# wssf_arduino_nano_client.net
KiCad netlist of a schematic drawn in EAGLE
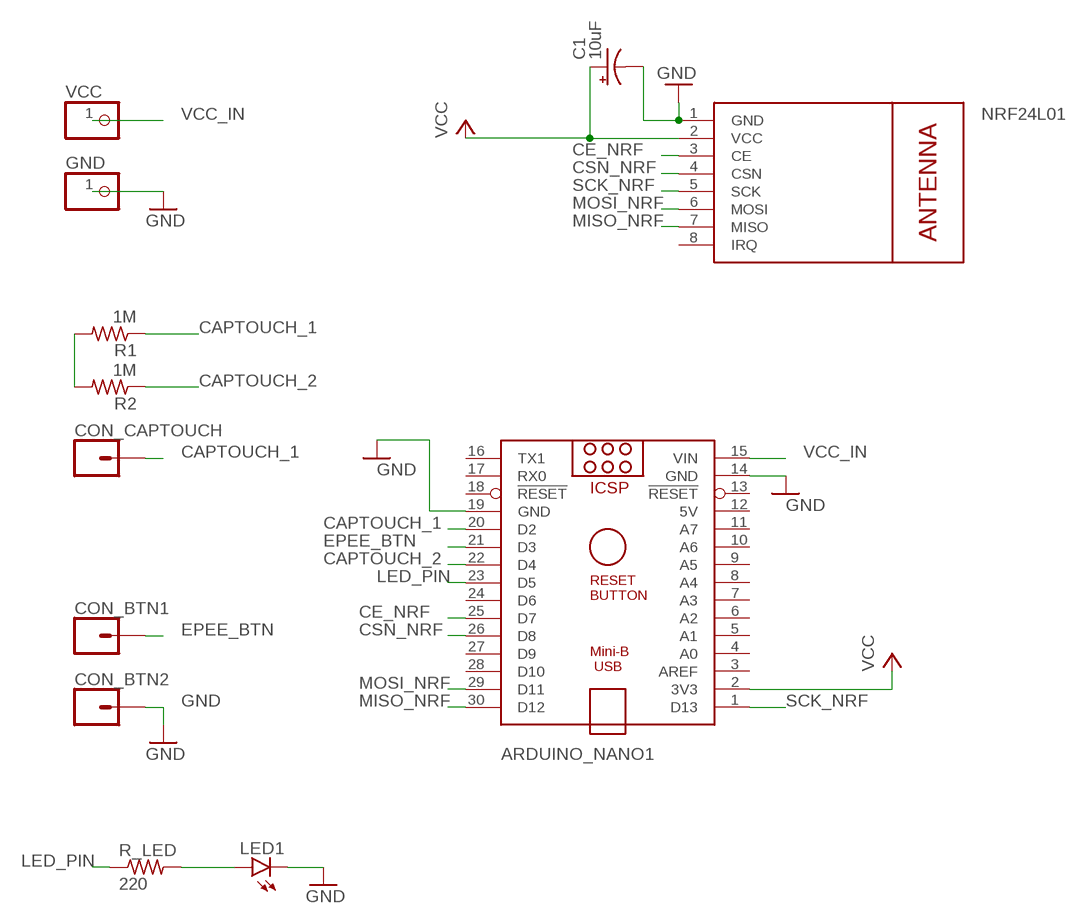
[diagram p0: schematic, sheet 1]

(export (version "E")
  (design (tool "Eeschema 10.0.6"))
  (components
    (comp (ref "ARDUINO_NANO1")
      (value "ARDUINO_NANO")
      (footprint "eagle-import:ARDUINO_NANO")
      (libsource (lib "eagle-import") (part "ARDUINO_NANO"))
    )
    (comp (ref "C1")
      (value "10uF")
      (footprint "eagle-import:E2-5")
      (libsource (lib "eagle-import") (part "CPOL-USE2-5"))
    )
    (comp (ref "CON_BTN1")
      (value "CONN_01")
      (footprint "eagle-import:1X01")
      (libsource (lib "eagle-import") (part "CONN_01"))
    )
    (comp (ref "CON_BTN2")
      (value "CONN_01")
      (footprint "eagle-import:1X01")
      (libsource (lib "eagle-import") (part "CONN_01"))
    )
    (comp (ref "CON_CAPTOUCH")
      (value "CONN_01")
      (footprint "eagle-import:1X01")
      (libsource (lib "eagle-import") (part "CONN_01"))
    )
    (comp (ref "GND")
      (value "PINHD-1X1")
      (footprint "eagle-import:1X01")
      (libsource (lib "eagle-import") (part "PINHD-1X1"))
    )
    (comp (ref "LED1")
      (value "LED5MM")
      (footprint "eagle-import:LED5MM")
      (libsource (lib "eagle-import") (part "LED5MM"))
    )
    (comp (ref "NRF24L01")
      (value "WIRELESS-NRF24L01")
      (footprint "eagle-import:WIRELESS-NRF24L01")
      (libsource (lib "eagle-import") (part "WIRELESS-NRF24L01"))
    )
    (comp (ref "R1")
      (value "1M")
      (footprint "eagle-import:0204_7")
      (libsource (lib "eagle-import") (part "R-US_0204/7"))
    )
    (comp (ref "R2")
      (value "1M")
      (footprint "eagle-import:0204_7")
      (libsource (lib "eagle-import") (part "R-US_0204/7"))
    )
    (comp (ref "R_LED")
      (value "220")
      (footprint "eagle-import:0204_7")
      (libsource (lib "eagle-import") (part "R-US_0204/7"))
    )
    (comp (ref "VCC")
      (value "PINHD-1X1")
      (footprint "eagle-import:1X01")
      (libsource (lib "eagle-import") (part "PINHD-1X1"))
    )
  )
  (nets
    (net (code "1") (name "/5V") (class "Default")
      (node (ref "ARDUINO_NANO1") (pin "12") (pinfunction "5V_12") (pintype "power_in"))
    )
    (net (code "2") (name "/CAPTOUCH_1") (class "Default")
      (node (ref "ARDUINO_NANO1") (pin "20") (pinfunction "D2_20") (pintype "bidirectional"))
      (node (ref "CON_CAPTOUCH") (pin "1") (pinfunction "1_1") (pintype "passive"))
      (node (ref "R1") (pin "1") (pinfunction "1_1") (pintype "passive"))
    )
    (net (code "3") (name "/CAPTOUCH_2") (class "Default")
      (node (ref "ARDUINO_NANO1") (pin "22") (pinfunction "D4_22") (pintype "bidirectional"))
      (node (ref "R2") (pin "1") (pinfunction "1_1") (pintype "passive"))
    )
    (net (code "4") (name "/CE_NRF") (class "Default")
      (node (ref "ARDUINO_NANO1") (pin "25") (pinfunction "D7_25") (pintype "bidirectional"))
      (node (ref "NRF24L01") (pin "3") (pinfunction "CE_3") (pintype "bidirectional"))
    )
    (net (code "5") (name "/CSN_NRF") (class "Default")
      (node (ref "ARDUINO_NANO1") (pin "26") (pinfunction "D8_26") (pintype "bidirectional"))
      (node (ref "NRF24L01") (pin "4") (pinfunction "CSN_4") (pintype "bidirectional"))
    )
    (net (code "6") (name "/EPEE_BTN") (class "Default")
      (node (ref "ARDUINO_NANO1") (pin "21") (pinfunction "D3_21") (pintype "bidirectional"))
      (node (ref "CON_BTN1") (pin "1") (pinfunction "1_1") (pintype "passive"))
    )
    (net (code "7") (name "/LED_PIN") (class "Default")
      (node (ref "ARDUINO_NANO1") (pin "23") (pinfunction "D5_23") (pintype "bidirectional"))
      (node (ref "R_LED") (pin "1") (pinfunction "1_1") (pintype "passive"))
    )
    (net (code "8") (name "/MISO_NRF") (class "Default")
      (node (ref "ARDUINO_NANO1") (pin "30") (pinfunction "D12_30") (pintype "bidirectional"))
      (node (ref "NRF24L01") (pin "7") (pinfunction "MISO_7") (pintype "bidirectional"))
    )
    (net (code "9") (name "/MOSI_NRF") (class "Default")
      (node (ref "ARDUINO_NANO1") (pin "29") (pinfunction "D11_29") (pintype "bidirectional"))
      (node (ref "NRF24L01") (pin "6") (pinfunction "MOSI_6") (pintype "bidirectional"))
    )
    (net (code "10") (name "/SCK_NRF") (class "Default")
      (node (ref "ARDUINO_NANO1") (pin "1") (pinfunction "D13_1") (pintype "bidirectional"))
      (node (ref "NRF24L01") (pin "5") (pinfunction "SCK_5") (pintype "bidirectional"))
    )
    (net (code "11") (name "/VCC_IN") (class "Default")
      (node (ref "ARDUINO_NANO1") (pin "15") (pinfunction "VIN_15") (pintype "power_in"))
      (node (ref "VCC") (pin "1") (pinfunction "1_1") (pintype "passive"))
    )
    (net (code "12") (name "GND") (class "Default")
      (node (ref "ARDUINO_NANO1") (pin "14") (pinfunction "GND_14") (pintype "power_in"))
      (node (ref "ARDUINO_NANO1") (pin "19") (pinfunction "GND_19") (pintype "power_in"))
      (node (ref "C1") (pin "-") (pinfunction "-_-") (pintype "passive"))
      (node (ref "CON_BTN2") (pin "1") (pinfunction "1_1") (pintype "passive"))
      (node (ref "GND") (pin "1") (pinfunction "1_1") (pintype "passive"))
      (node (ref "LED1") (pin "K") (pinfunction "C_K") (pintype "passive"))
      (node (ref "NRF24L01") (pin "1") (pinfunction "GND_1") (pintype "power_in"))
    )
    (net (code "13") (name "Net-(LED1-PadA)") (class "Default")
      (node (ref "LED1") (pin "A") (pinfunction "A_A") (pintype "passive"))
      (node (ref "R_LED") (pin "2") (pinfunction "2_2") (pintype "passive"))
    )
    (net (code "14") (name "Net-(R1-Pad2)") (class "Default")
      (node (ref "R1") (pin "2") (pinfunction "2_2") (pintype "passive"))
      (node (ref "R2") (pin "2") (pinfunction "2_2") (pintype "passive"))
    )
    (net (code "15") (name "VCC") (class "Default")
      (node (ref "ARDUINO_NANO1") (pin "2") (pinfunction "3V3_2") (pintype "output"))
      (node (ref "C1") (pin "+") (pinfunction "+_+") (pintype "passive"))
      (node (ref "NRF24L01") (pin "2") (pinfunction "VCC_2") (pintype "power_in"))
    )
    (net (code "16") (name "unconnected-(ARDUINO_NANO1-A0-Pad4)") (class "Default")
      (node (ref "ARDUINO_NANO1") (pin "4") (pinfunction "A0_4") (pintype "bidirectional"))
    )
    (net (code "17") (name "unconnected-(ARDUINO_NANO1-A1-Pad5)") (class "Default")
      (node (ref "ARDUINO_NANO1") (pin "5") (pinfunction "A1_5") (pintype "bidirectional"))
    )
    (net (code "18") (name "unconnected-(ARDUINO_NANO1-A2-Pad6)") (class "Default")
      (node (ref "ARDUINO_NANO1") (pin "6") (pinfunction "A2_6") (pintype "bidirectional"))
    )
    (net (code "19") (name "unconnected-(ARDUINO_NANO1-A3-Pad7)") (class "Default")
      (node (ref "ARDUINO_NANO1") (pin "7") (pinfunction "A3_7") (pintype "bidirectional"))
    )
    (net (code "20") (name "unconnected-(ARDUINO_NANO1-A4-Pad8)") (class "Default")
      (node (ref "ARDUINO_NANO1") (pin "8") (pinfunction "A4_8") (pintype "bidirectional"))
    )
    (net (code "21") (name "unconnected-(ARDUINO_NANO1-A5-Pad9)") (class "Default")
      (node (ref "ARDUINO_NANO1") (pin "9") (pinfunction "A5_9") (pintype "bidirectional"))
    )
    (net (code "22") (name "unconnected-(ARDUINO_NANO1-A6-Pad10)") (class "Default")
      (node (ref "ARDUINO_NANO1") (pin "10") (pinfunction "A6_10") (pintype "bidirectional"))
    )
    (net (code "23") (name "unconnected-(ARDUINO_NANO1-A7-Pad11)") (class "Default")
      (node (ref "ARDUINO_NANO1") (pin "11") (pinfunction "A7_11") (pintype "bidirectional"))
    )
    (net (code "24") (name "unconnected-(ARDUINO_NANO1-AREF-Pad3)") (class "Default")
      (node (ref "ARDUINO_NANO1") (pin "3") (pinfunction "AREF_3") (pintype "input"))
    )
    (net (code "25") (name "unconnected-(ARDUINO_NANO1-D6-Pad24)") (class "Default")
      (node (ref "ARDUINO_NANO1") (pin "24") (pinfunction "D6_24") (pintype "bidirectional"))
    )
    (net (code "26") (name "unconnected-(ARDUINO_NANO1-D9-Pad27)") (class "Default")
      (node (ref "ARDUINO_NANO1") (pin "27") (pinfunction "D9_27") (pintype "bidirectional"))
    )
    (net (code "27") (name "unconnected-(ARDUINO_NANO1-D10-Pad28)") (class "Default")
      (node (ref "ARDUINO_NANO1") (pin "28") (pinfunction "D10_28") (pintype "bidirectional"))
    )
    (net (code "28") (name "unconnected-(ARDUINO_NANO1-RX0-Pad17)") (class "Default")
      (node (ref "ARDUINO_NANO1") (pin "17") (pinfunction "RX0_17") (pintype "bidirectional"))
    )
    (net (code "29") (name "unconnected-(ARDUINO_NANO1-TX1-Pad16)") (class "Default")
      (node (ref "ARDUINO_NANO1") (pin "16") (pinfunction "TX1_16") (pintype "bidirectional"))
    )
    (net (code "30") (name "unconnected-(ARDUINO_NANO1-~{RESET}-Pad13)") (class "Default")
      (node (ref "ARDUINO_NANO1") (pin "13") (pinfunction "~{RESET}_13") (pintype "input"))
    )
    (net (code "31") (name "unconnected-(ARDUINO_NANO1-~{RESET}-Pad18)") (class "Default")
      (node (ref "ARDUINO_NANO1") (pin "18") (pinfunction "~{RESET}_18") (pintype "input"))
    )
    (net (code "32") (name "unconnected-(NRF24L01-IRQ-Pad8)") (class "Default")
      (node (ref "NRF24L01") (pin "8") (pinfunction "IRQ_8") (pintype "bidirectional"))
    )
  )
)
